# hwre.net
KiCad netlist of a schematic drawn in EAGLE
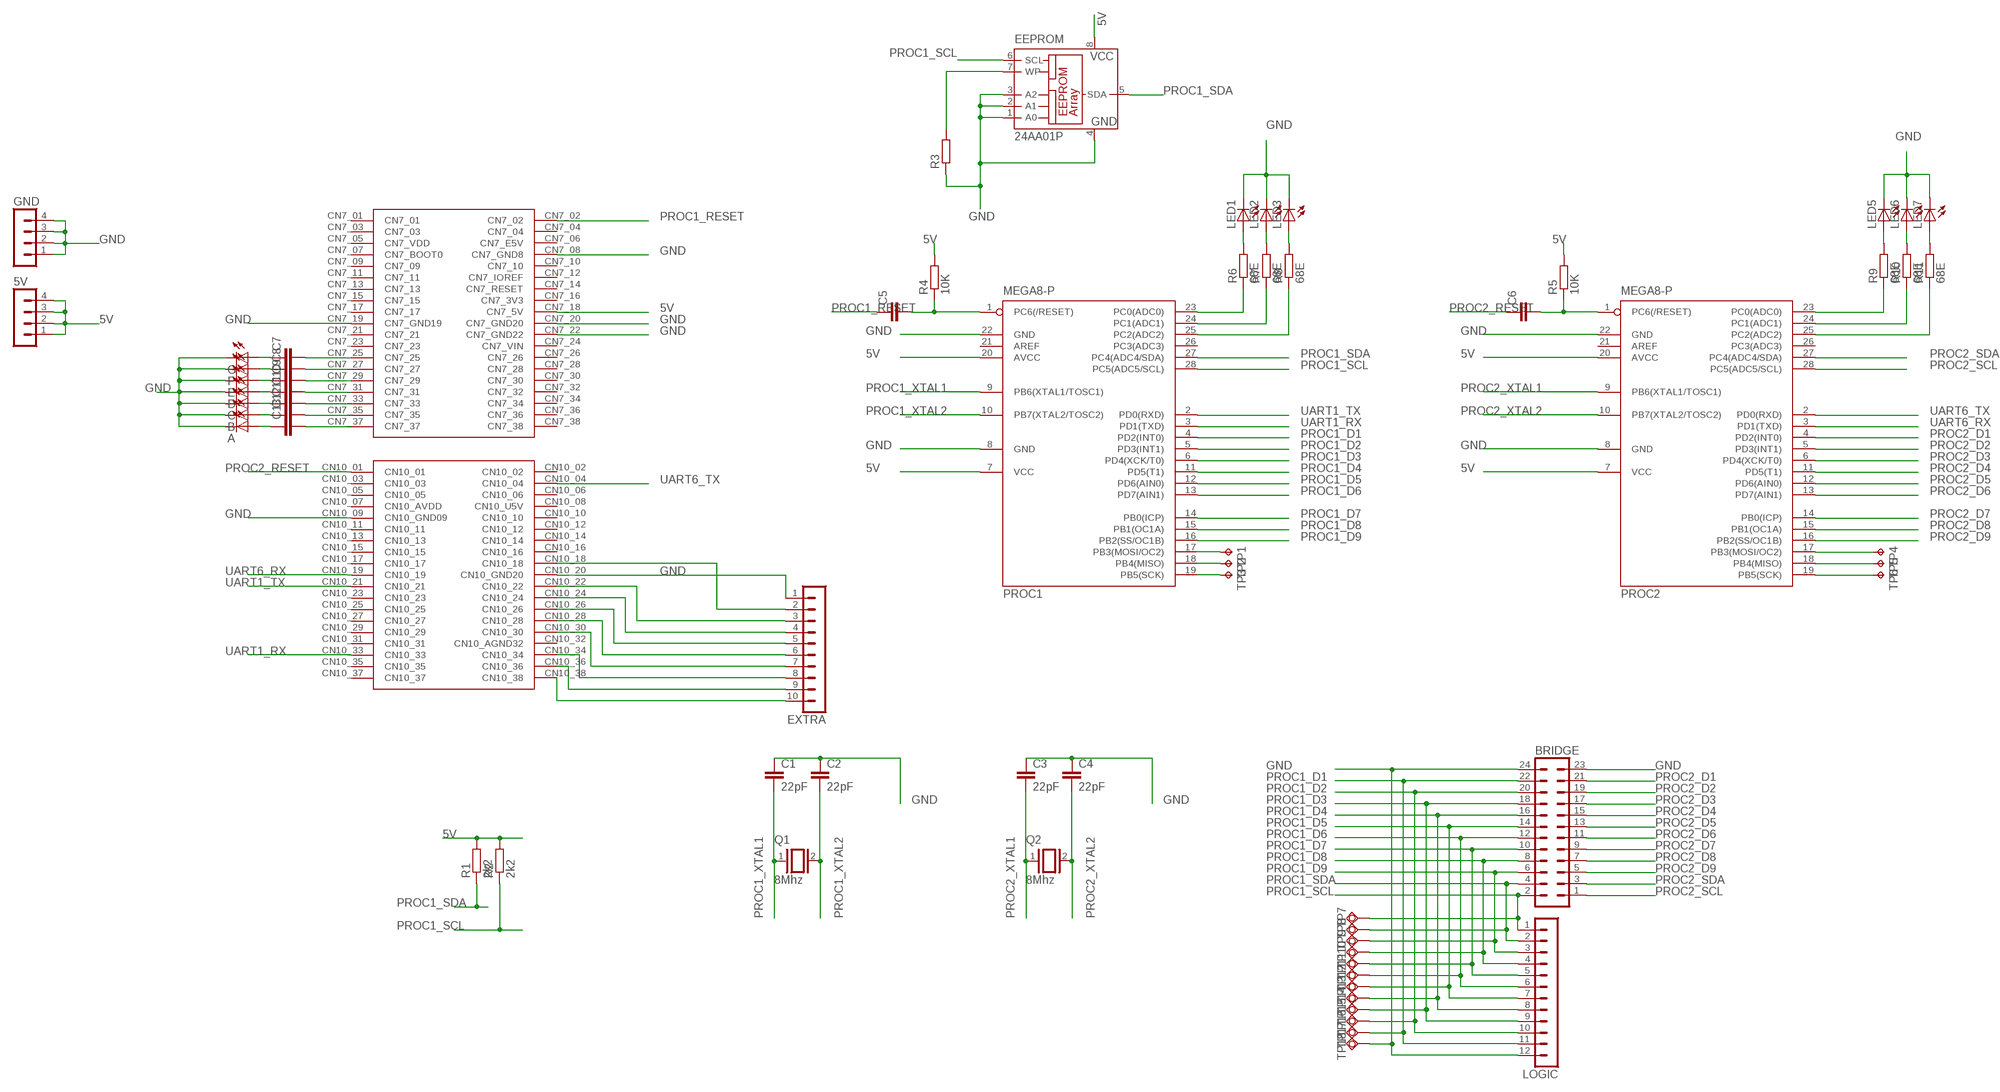
[diagram p0: schematic, sheet 1]

(export (version "E")
  (design (tool "Eeschema 10.0.6"))
  (components
    (comp (ref "5V")
      (value "MA04-1")
      (footprint "eagle-import:MA04-1")
      (libsource (lib "eagle-import") (part "MA04-1"))
    )
    (comp (ref "A")
      (value "LEDCHIP-LED0603")
      (footprint "eagle-import:CHIP-LED0603")
      (libsource (lib "eagle-import") (part "LEDCHIP-LED0603"))
    )
    (comp (ref "B")
      (value "LEDCHIP-LED0603")
      (footprint "eagle-import:CHIP-LED0603")
      (libsource (lib "eagle-import") (part "LEDCHIP-LED0603"))
    )
    (comp (ref "BRIDGE")
      (value "MA12-2")
      (footprint "eagle-import:MA12-2")
      (libsource (lib "eagle-import") (part "MA12-2"))
    )
    (comp (ref "C")
      (value "LEDCHIP-LED0603")
      (footprint "eagle-import:CHIP-LED0603")
      (libsource (lib "eagle-import") (part "LEDCHIP-LED0603"))
    )
    (comp (ref "C1")
      (value "22pF")
      (footprint "eagle-import:C0603")
      (libsource (lib "eagle-import") (part "C-EUC0603"))
    )
    (comp (ref "C2")
      (value "22pF")
      (footprint "eagle-import:C0603")
      (libsource (lib "eagle-import") (part "C-EUC0603"))
    )
    (comp (ref "C3")
      (value "22pF")
      (footprint "eagle-import:C0603")
      (libsource (lib "eagle-import") (part "C-EUC0603"))
    )
    (comp (ref "C4")
      (value "22pF")
      (footprint "eagle-import:C0603")
      (libsource (lib "eagle-import") (part "C-EUC0603"))
    )
    (comp (ref "C5")
      (value "C-EUC0603")
      (footprint "eagle-import:C0603")
      (libsource (lib "eagle-import") (part "C-EUC0603"))
    )
    (comp (ref "C6")
      (value "C-EUC0603")
      (footprint "eagle-import:C0603")
      (libsource (lib "eagle-import") (part "C-EUC0603"))
    )
    (comp (ref "C7")
      (value "C-EUC0603")
      (footprint "eagle-import:C0603")
      (libsource (lib "eagle-import") (part "C-EUC0603"))
    )
    (comp (ref "C8")
      (value "C-EUC0603")
      (footprint "eagle-import:C0603")
      (libsource (lib "eagle-import") (part "C-EUC0603"))
    )
    (comp (ref "C9")
      (value "C-EUC0603")
      (footprint "eagle-import:C0603")
      (libsource (lib "eagle-import") (part "C-EUC0603"))
    )
    (comp (ref "C10")
      (value "C-EUC0603")
      (footprint "eagle-import:C0603")
      (libsource (lib "eagle-import") (part "C-EUC0603"))
    )
    (comp (ref "C11")
      (value "C-EUC0603")
      (footprint "eagle-import:C0603")
      (libsource (lib "eagle-import") (part "C-EUC0603"))
    )
    (comp (ref "C12")
      (value "C-EUC0603")
      (footprint "eagle-import:C0603")
      (libsource (lib "eagle-import") (part "C-EUC0603"))
    )
    (comp (ref "C13")
      (value "C-EUC0603")
      (footprint "eagle-import:C0603")
      (libsource (lib "eagle-import") (part "C-EUC0603"))
    )
    (comp (ref "D")
      (value "LEDCHIP-LED0603")
      (footprint "eagle-import:CHIP-LED0603")
      (libsource (lib "eagle-import") (part "LEDCHIP-LED0603"))
    )
    (comp (ref "E")
      (value "LEDCHIP-LED0603")
      (footprint "eagle-import:CHIP-LED0603")
      (libsource (lib "eagle-import") (part "LEDCHIP-LED0603"))
    )
    (comp (ref "EEPROM")
      (value "24AA01P")
      (footprint "eagle-import:DIL8")
      (fields (field (name "MPN") "24AA01-I/P"))
      (libsource (lib "eagle-import") (part "24PAA01"))
    )
    (comp (ref "EXTRA")
      (value "MA10-1")
      (footprint "eagle-import:MA10-1")
      (libsource (lib "eagle-import") (part "MA10-1"))
    )
    (comp (ref "F")
      (value "LEDCHIP-LED0603")
      (footprint "eagle-import:CHIP-LED0603")
      (libsource (lib "eagle-import") (part "LEDCHIP-LED0603"))
    )
    (comp (ref "G")
      (value "LEDCHIP-LED0603")
      (footprint "eagle-import:CHIP-LED0603")
      (libsource (lib "eagle-import") (part "LEDCHIP-LED0603"))
    )
    (comp (ref "GND")
      (value "MA04-1")
      (footprint "eagle-import:MA04-1")
      (libsource (lib "eagle-import") (part "MA04-1"))
    )
    (comp (ref "LED1")
      (value "LEDSML0805")
      (footprint "eagle-import:SML0805")
      (libsource (lib "eagle-import") (part "LEDSML0805"))
    )
    (comp (ref "LED2")
      (value "LEDSML0805")
      (footprint "eagle-import:SML0805")
      (libsource (lib "eagle-import") (part "LEDSML0805"))
    )
    (comp (ref "LED3")
      (value "LEDSML0805")
      (footprint "eagle-import:SML0805")
      (libsource (lib "eagle-import") (part "LEDSML0805"))
    )
    (comp (ref "LED5")
      (value "LEDSML0805")
      (footprint "eagle-import:SML0805")
      (libsource (lib "eagle-import") (part "LEDSML0805"))
    )
    (comp (ref "LED6")
      (value "LEDSML0805")
      (footprint "eagle-import:SML0805")
      (libsource (lib "eagle-import") (part "LEDSML0805"))
    )
    (comp (ref "LED7")
      (value "LEDSML0805")
      (footprint "eagle-import:SML0805")
      (libsource (lib "eagle-import") (part "LEDSML0805"))
    )
    (comp (ref "LOGIC")
      (value "MA12-1")
      (footprint "eagle-import:MA12-1")
      (libsource (lib "eagle-import") (part "MA12-1"))
    )
    (comp (ref "PROC1")
      (value "MEGA8-P")
      (footprint "eagle-import:DIL28-3")
      (libsource (lib "eagle-import") (part "MEGA8-P"))
    )
    (comp (ref "PROC2")
      (value "MEGA8-P")
      (footprint "eagle-import:DIL28-3")
      (libsource (lib "eagle-import") (part "MEGA8-P"))
    )
    (comp (ref "Q1")
      (value "8Mhz")
      (footprint "eagle-import:QS")
      (libsource (lib "eagle-import") (part "XTAL/S"))
    )
    (comp (ref "Q2")
      (value "8Mhz")
      (footprint "eagle-import:QS")
      (libsource (lib "eagle-import") (part "XTAL/S"))
    )
    (comp (ref "R1")
      (value "2k2")
      (footprint "eagle-import:R0603")
      (libsource (lib "eagle-import") (part "R-EU_R0603"))
    )
    (comp (ref "R2")
      (value "2k2")
      (footprint "eagle-import:R0603")
      (libsource (lib "eagle-import") (part "R-EU_R0603"))
    )
    (comp (ref "R3")
      (value "R-EU_R0603")
      (footprint "eagle-import:R0603")
      (libsource (lib "eagle-import") (part "resistor_R-EU_R0603"))
    )
    (comp (ref "R4")
      (value "10K")
      (footprint "eagle-import:R0603")
      (libsource (lib "eagle-import") (part "resistor_R-EU_R0603"))
    )
    (comp (ref "R5")
      (value "10K")
      (footprint "eagle-import:R0603")
      (libsource (lib "eagle-import") (part "resistor_R-EU_R0603"))
    )
    (comp (ref "R6")
      (value "68E")
      (footprint "eagle-import:R0603")
      (libsource (lib "eagle-import") (part "R-EU_R0603"))
    )
    (comp (ref "R7")
      (value "68E")
      (footprint "eagle-import:R0603")
      (libsource (lib "eagle-import") (part "R-EU_R0603"))
    )
    (comp (ref "R8")
      (value "68E")
      (footprint "eagle-import:R0603")
      (libsource (lib "eagle-import") (part "R-EU_R0603"))
    )
    (comp (ref "R9")
      (value "68E")
      (footprint "eagle-import:R0603")
      (libsource (lib "eagle-import") (part "R-EU_R0603"))
    )
    (comp (ref "R10")
      (value "68E")
      (footprint "eagle-import:R0603")
      (libsource (lib "eagle-import") (part "R-EU_R0603"))
    )
    (comp (ref "R11")
      (value "68E")
      (footprint "eagle-import:R0603")
      (libsource (lib "eagle-import") (part "R-EU_R0603"))
    )
    (comp (ref "TP1")
      (value "TPTP20R")
      (footprint "eagle-import:TP20R")
      (libsource (lib "eagle-import") (part "TPTP20R"))
    )
    (comp (ref "TP2")
      (value "TPTP20R")
      (footprint "eagle-import:TP20R")
      (libsource (lib "eagle-import") (part "TPTP20R"))
    )
    (comp (ref "TP3")
      (value "TPTP20R")
      (footprint "eagle-import:TP20R")
      (libsource (lib "eagle-import") (part "TPTP20R"))
    )
    (comp (ref "TP4")
      (value "TPTP20R")
      (footprint "eagle-import:TP20R")
      (libsource (lib "eagle-import") (part "TPTP20R"))
    )
    (comp (ref "TP5")
      (value "TPTP20R")
      (footprint "eagle-import:TP20R")
      (libsource (lib "eagle-import") (part "TPTP20R"))
    )
    (comp (ref "TP6")
      (value "TPTP20R")
      (footprint "eagle-import:TP20R")
      (libsource (lib "eagle-import") (part "TPTP20R"))
    )
    (comp (ref "TP7")
      (value "TPSQTP20R")
      (footprint "eagle-import:TP20R")
      (libsource (lib "eagle-import") (part "TPSQTP20R"))
    )
    (comp (ref "TP8")
      (value "TPSQTP20R")
      (footprint "eagle-import:TP20R")
      (libsource (lib "eagle-import") (part "TPSQTP20R"))
    )
    (comp (ref "TP9")
      (value "TPSQTP20R")
      (footprint "eagle-import:TP20R")
      (libsource (lib "eagle-import") (part "TPSQTP20R"))
    )
    (comp (ref "TP10")
      (value "TPSQTP20R")
      (footprint "eagle-import:TP20R")
      (libsource (lib "eagle-import") (part "TPSQTP20R"))
    )
    (comp (ref "TP11")
      (value "TPSQTP20R")
      (footprint "eagle-import:TP20R")
      (libsource (lib "eagle-import") (part "TPSQTP20R"))
    )
    (comp (ref "TP12")
      (value "TPSQTP20R")
      (footprint "eagle-import:TP20R")
      (libsource (lib "eagle-import") (part "TPSQTP20R"))
    )
    (comp (ref "TP13")
      (value "TPSQTP20R")
      (footprint "eagle-import:TP20R")
      (libsource (lib "eagle-import") (part "TPSQTP20R"))
    )
    (comp (ref "TP14")
      (value "TPSQTP20R")
      (footprint "eagle-import:TP20R")
      (libsource (lib "eagle-import") (part "TPSQTP20R"))
    )
    (comp (ref "TP15")
      (value "TPSQTP20R")
      (footprint "eagle-import:TP20R")
      (libsource (lib "eagle-import") (part "TPSQTP20R"))
    )
    (comp (ref "TP16")
      (value "TPSQTP20R")
      (footprint "eagle-import:TP20R")
      (libsource (lib "eagle-import") (part "TPSQTP20R"))
    )
    (comp (ref "TP17")
      (value "TPSQTP20R")
      (footprint "eagle-import:TP20R")
      (libsource (lib "eagle-import") (part "TPSQTP20R"))
    )
    (comp (ref "TP18")
      (value "TPSQTP20R")
      (footprint "eagle-import:TP20R")
      (libsource (lib "eagle-import") (part "TPSQTP20R"))
    )
    (comp (ref "U$1")
      (value "NUCLEO_SHIELDGENERIC")
      (footprint "eagle-import:NUCLEO_SHIELD")
      (libsource (lib "eagle-import") (part "NUCLEO_SHIELDGENERIC"))
    )
  )
  (nets
    (net (code "1") (name "/5V") (class "Default")
      (node (ref "5V") (pin "1") (pinfunction "1_1") (pintype "passive"))
      (node (ref "5V") (pin "2") (pinfunction "2_2") (pintype "passive"))
      (node (ref "5V") (pin "3") (pinfunction "3_3") (pintype "passive"))
      (node (ref "5V") (pin "4") (pinfunction "4_4") (pintype "passive"))
      (node (ref "EEPROM") (pin "8") (pinfunction "VCC_8") (pintype "power_in"))
      (node (ref "PROC1") (pin "20") (pinfunction "AVCC_20") (pintype "power_in"))
      (node (ref "PROC1") (pin "7") (pinfunction "VCC_7") (pintype "power_in"))
      (node (ref "PROC2") (pin "20") (pinfunction "AVCC_20") (pintype "power_in"))
      (node (ref "PROC2") (pin "7") (pinfunction "VCC_7") (pintype "power_in"))
      (node (ref "R1") (pin "2") (pinfunction "2_2") (pintype "passive"))
      (node (ref "R2") (pin "2") (pinfunction "2_2") (pintype "passive"))
      (node (ref "R4") (pin "2") (pinfunction "2_2") (pintype "passive"))
      (node (ref "R5") (pin "2") (pinfunction "2_2") (pintype "passive"))
      (node (ref "U$1") (pin "CN7_18") (pinfunction "CN7_5V_CN7_18") (pintype "bidirectional"))
    )
    (net (code "2") (name "/GND") (class "Default")
      (node (ref "A") (pin "C") (pinfunction "C_C") (pintype "passive"))
      (node (ref "B") (pin "C") (pinfunction "C_C") (pintype "passive"))
      (node (ref "BRIDGE") (pin "23") (pinfunction "23_23") (pintype "passive"))
      (node (ref "BRIDGE") (pin "24") (pinfunction "24_24") (pintype "passive"))
      (node (ref "C") (pin "C") (pinfunction "C_C") (pintype "passive"))
      (node (ref "C1") (pin "1") (pinfunction "1_1") (pintype "passive"))
      (node (ref "C2") (pin "1") (pinfunction "1_1") (pintype "passive"))
      (node (ref "C3") (pin "1") (pinfunction "1_1") (pintype "passive"))
      (node (ref "C4") (pin "1") (pinfunction "1_1") (pintype "passive"))
      (node (ref "D") (pin "C") (pinfunction "C_C") (pintype "passive"))
      (node (ref "E") (pin "C") (pinfunction "C_C") (pintype "passive"))
      (node (ref "EEPROM") (pin "1") (pinfunction "A0_1") (pintype "input"))
      (node (ref "EEPROM") (pin "2") (pinfunction "A1_2") (pintype "input"))
      (node (ref "EEPROM") (pin "3") (pinfunction "A2_3") (pintype "input"))
      (node (ref "EEPROM") (pin "4") (pinfunction "GND_4") (pintype "power_in"))
      (node (ref "EXTRA") (pin "1") (pinfunction "1_1") (pintype "passive"))
      (node (ref "F") (pin "C") (pinfunction "C_C") (pintype "passive"))
      (node (ref "G") (pin "C") (pinfunction "C_C") (pintype "passive"))
      (node (ref "GND") (pin "1") (pinfunction "1_1") (pintype "passive"))
      (node (ref "GND") (pin "2") (pinfunction "2_2") (pintype "passive"))
      (node (ref "GND") (pin "3") (pinfunction "3_3") (pintype "passive"))
      (node (ref "GND") (pin "4") (pinfunction "4_4") (pintype "passive"))
      (node (ref "LED1") (pin "C") (pinfunction "C_C") (pintype "passive"))
      (node (ref "LED2") (pin "C") (pinfunction "C_C") (pintype "passive"))
      (node (ref "LED3") (pin "C") (pinfunction "C_C") (pintype "passive"))
      (node (ref "LED5") (pin "C") (pinfunction "C_C") (pintype "passive"))
      (node (ref "LED6") (pin "C") (pinfunction "C_C") (pintype "passive"))
      (node (ref "LED7") (pin "C") (pinfunction "C_C") (pintype "passive"))
      (node (ref "LOGIC") (pin "12") (pinfunction "12_12") (pintype "passive"))
      (node (ref "PROC1") (pin "22") (pinfunction "GND_22") (pintype "power_in"))
      (node (ref "PROC1") (pin "8") (pinfunction "GND_8") (pintype "power_in"))
      (node (ref "PROC2") (pin "22") (pinfunction "GND_22") (pintype "power_in"))
      (node (ref "PROC2") (pin "8") (pinfunction "GND_8") (pintype "power_in"))
      (node (ref "R3") (pin "1") (pinfunction "1_1") (pintype "passive"))
      (node (ref "TP18") (pin "TP") (pinfunction "TP_TP") (pintype "input"))
      (node (ref "U$1") (pin "CN10_09") (pinfunction "CN10_GND09_CN10_09") (pintype "bidirectional"))
      (node (ref "U$1") (pin "CN10_20") (pinfunction "CN10_GND20_CN10_20") (pintype "bidirectional"))
      (node (ref "U$1") (pin "CN7_08") (pinfunction "CN7_GND8_CN7_08") (pintype "bidirectional"))
      (node (ref "U$1") (pin "CN7_19") (pinfunction "CN7_GND19_CN7_19") (pintype "bidirectional"))
      (node (ref "U$1") (pin "CN7_20") (pinfunction "CN7_GND20_CN7_20") (pintype "bidirectional"))
      (node (ref "U$1") (pin "CN7_22") (pinfunction "CN7_GND22_CN7_22") (pintype "bidirectional"))
    )
    (net (code "3") (name "/PROC1_D1") (class "Default")
      (node (ref "BRIDGE") (pin "22") (pinfunction "22_22") (pintype "passive"))
      (node (ref "LOGIC") (pin "11") (pinfunction "11_11") (pintype "passive"))
      (node (ref "PROC1") (pin "4") (pinfunction "PD2(INT0)_4") (pintype "bidirectional"))
      (node (ref "TP17") (pin "TP") (pinfunction "TP_TP") (pintype "input"))
    )
    (net (code "4") (name "/PROC1_D2") (class "Default")
      (node (ref "BRIDGE") (pin "20") (pinfunction "20_20") (pintype "passive"))
      (node (ref "LOGIC") (pin "10") (pinfunction "10_10") (pintype "passive"))
      (node (ref "PROC1") (pin "5") (pinfunction "PD3(INT1)_5") (pintype "bidirectional"))
      (node (ref "TP16") (pin "TP") (pinfunction "TP_TP") (pintype "input"))
    )
    (net (code "5") (name "/PROC1_D3") (class "Default")
      (node (ref "BRIDGE") (pin "18") (pinfunction "18_18") (pintype "passive"))
      (node (ref "LOGIC") (pin "9") (pinfunction "9_9") (pintype "passive"))
      (node (ref "PROC1") (pin "6") (pinfunction "PD4(XCK/T0)_6") (pintype "bidirectional"))
      (node (ref "TP15") (pin "TP") (pinfunction "TP_TP") (pintype "input"))
    )
    (net (code "6") (name "/PROC1_D4") (class "Default")
      (node (ref "BRIDGE") (pin "16") (pinfunction "16_16") (pintype "passive"))
      (node (ref "LOGIC") (pin "8") (pinfunction "8_8") (pintype "passive"))
      (node (ref "PROC1") (pin "11") (pinfunction "PD5(T1)_11") (pintype "bidirectional"))
      (node (ref "TP14") (pin "TP") (pinfunction "TP_TP") (pintype "input"))
    )
    (net (code "7") (name "/PROC1_D5") (class "Default")
      (node (ref "BRIDGE") (pin "14") (pinfunction "14_14") (pintype "passive"))
      (node (ref "LOGIC") (pin "7") (pinfunction "7_7") (pintype "passive"))
      (node (ref "PROC1") (pin "12") (pinfunction "PD6(AIN0)_12") (pintype "bidirectional"))
      (node (ref "TP13") (pin "TP") (pinfunction "TP_TP") (pintype "input"))
    )
    (net (code "8") (name "/PROC1_D6") (class "Default")
      (node (ref "BRIDGE") (pin "12") (pinfunction "12_12") (pintype "passive"))
      (node (ref "LOGIC") (pin "6") (pinfunction "6_6") (pintype "passive"))
      (node (ref "PROC1") (pin "13") (pinfunction "PD7(AIN1)_13") (pintype "bidirectional"))
      (node (ref "TP12") (pin "TP") (pinfunction "TP_TP") (pintype "input"))
    )
    (net (code "9") (name "/PROC1_D7") (class "Default")
      (node (ref "BRIDGE") (pin "10") (pinfunction "10_10") (pintype "passive"))
      (node (ref "LOGIC") (pin "5") (pinfunction "5_5") (pintype "passive"))
      (node (ref "PROC1") (pin "14") (pinfunction "PB0(ICP)_14") (pintype "bidirectional"))
      (node (ref "TP11") (pin "TP") (pinfunction "TP_TP") (pintype "input"))
    )
    (net (code "10") (name "/PROC1_D8") (class "Default")
      (node (ref "BRIDGE") (pin "8") (pinfunction "8_8") (pintype "passive"))
      (node (ref "LOGIC") (pin "4") (pinfunction "4_4") (pintype "passive"))
      (node (ref "PROC1") (pin "15") (pinfunction "PB1(OC1A)_15") (pintype "bidirectional"))
      (node (ref "TP10") (pin "TP") (pinfunction "TP_TP") (pintype "input"))
    )
    (net (code "11") (name "/PROC1_D9") (class "Default")
      (node (ref "BRIDGE") (pin "6") (pinfunction "6_6") (pintype "passive"))
      (node (ref "LOGIC") (pin "3") (pinfunction "3_3") (pintype "passive"))
      (node (ref "PROC1") (pin "16") (pinfunction "PB2(SS/OC1B)_16") (pintype "bidirectional"))
      (node (ref "TP9") (pin "TP") (pinfunction "TP_TP") (pintype "input"))
    )
    (net (code "12") (name "/PROC1_RESET") (class "Default")
      (node (ref "C5") (pin "1") (pinfunction "1_1") (pintype "passive"))
      (node (ref "U$1") (pin "CN7_02") (pinfunction "CN7_02_CN7_02") (pintype "bidirectional"))
    )
    (net (code "13") (name "/PROC1_SCL") (class "Default")
      (node (ref "BRIDGE") (pin "2") (pinfunction "2_2") (pintype "passive"))
      (node (ref "EEPROM") (pin "6") (pinfunction "SCL_6") (pintype "input"))
      (node (ref "LOGIC") (pin "1") (pinfunction "1_1") (pintype "passive"))
      (node (ref "PROC1") (pin "28") (pinfunction "PC5(ADC5/SCL)_28") (pintype "bidirectional"))
      (node (ref "R2") (pin "1") (pinfunction "1_1") (pintype "passive"))
      (node (ref "TP7") (pin "TP") (pinfunction "TP_TP") (pintype "input"))
    )
    (net (code "14") (name "/PROC1_SDA") (class "Default")
      (node (ref "BRIDGE") (pin "4") (pinfunction "4_4") (pintype "passive"))
      (node (ref "EEPROM") (pin "5") (pinfunction "SDA_5") (pintype "bidirectional"))
      (node (ref "LOGIC") (pin "2") (pinfunction "2_2") (pintype "passive"))
      (node (ref "PROC1") (pin "27") (pinfunction "PC4(ADC4/SDA)_27") (pintype "bidirectional"))
      (node (ref "R1") (pin "1") (pinfunction "1_1") (pintype "passive"))
      (node (ref "TP8") (pin "TP") (pinfunction "TP_TP") (pintype "input"))
    )
    (net (code "15") (name "/PROC1_XTAL1") (class "Default")
      (node (ref "C1") (pin "2") (pinfunction "2_2") (pintype "passive"))
      (node (ref "PROC1") (pin "9") (pinfunction "PB6(XTAL1/TOSC1)_9") (pintype "bidirectional"))
      (node (ref "Q1") (pin "1") (pinfunction "1_1") (pintype "passive"))
    )
    (net (code "16") (name "/PROC1_XTAL2") (class "Default")
      (node (ref "C2") (pin "2") (pinfunction "2_2") (pintype "passive"))
      (node (ref "PROC1") (pin "10") (pinfunction "PB7(XTAL2/TOSC2)_10") (pintype "bidirectional"))
      (node (ref "Q1") (pin "2") (pinfunction "2_2") (pintype "passive"))
    )
    (net (code "17") (name "/PROC2_D1") (class "Default")
      (node (ref "BRIDGE") (pin "21") (pinfunction "21_21") (pintype "passive"))
      (node (ref "PROC2") (pin "4") (pinfunction "PD2(INT0)_4") (pintype "bidirectional"))
    )
    (net (code "18") (name "/PROC2_D2") (class "Default")
      (node (ref "BRIDGE") (pin "19") (pinfunction "19_19") (pintype "passive"))
      (node (ref "PROC2") (pin "5") (pinfunction "PD3(INT1)_5") (pintype "bidirectional"))
    )
    (net (code "19") (name "/PROC2_D3") (class "Default")
      (node (ref "BRIDGE") (pin "17") (pinfunction "17_17") (pintype "passive"))
      (node (ref "PROC2") (pin "6") (pinfunction "PD4(XCK/T0)_6") (pintype "bidirectional"))
    )
    (net (code "20") (name "/PROC2_D4") (class "Default")
      (node (ref "BRIDGE") (pin "15") (pinfunction "15_15") (pintype "passive"))
      (node (ref "PROC2") (pin "11") (pinfunction "PD5(T1)_11") (pintype "bidirectional"))
    )
    (net (code "21") (name "/PROC2_D5") (class "Default")
      (node (ref "BRIDGE") (pin "13") (pinfunction "13_13") (pintype "passive"))
      (node (ref "PROC2") (pin "12") (pinfunction "PD6(AIN0)_12") (pintype "bidirectional"))
    )
    (net (code "22") (name "/PROC2_D6") (class "Default")
      (node (ref "BRIDGE") (pin "11") (pinfunction "11_11") (pintype "passive"))
      (node (ref "PROC2") (pin "13") (pinfunction "PD7(AIN1)_13") (pintype "bidirectional"))
    )
    (net (code "23") (name "/PROC2_D7") (class "Default")
      (node (ref "BRIDGE") (pin "9") (pinfunction "9_9") (pintype "passive"))
      (node (ref "PROC2") (pin "14") (pinfunction "PB0(ICP)_14") (pintype "bidirectional"))
    )
    (net (code "24") (name "/PROC2_D8") (class "Default")
      (node (ref "BRIDGE") (pin "7") (pinfunction "7_7") (pintype "passive"))
      (node (ref "PROC2") (pin "15") (pinfunction "PB1(OC1A)_15") (pintype "bidirectional"))
    )
    (net (code "25") (name "/PROC2_D9") (class "Default")
      (node (ref "BRIDGE") (pin "5") (pinfunction "5_5") (pintype "passive"))
      (node (ref "PROC2") (pin "16") (pinfunction "PB2(SS/OC1B)_16") (pintype "bidirectional"))
    )
    (net (code "26") (name "/PROC2_RESET") (class "Default")
      (node (ref "C6") (pin "1") (pinfunction "1_1") (pintype "passive"))
      (node (ref "U$1") (pin "CN10_01") (pinfunction "CN10_01_CN10_01") (pintype "bidirectional"))
    )
    (net (code "27") (name "/PROC2_SCL") (class "Default")
      (node (ref "BRIDGE") (pin "1") (pinfunction "1_1") (pintype "passive"))
      (node (ref "PROC2") (pin "28") (pinfunction "PC5(ADC5/SCL)_28") (pintype "bidirectional"))
    )
    (net (code "28") (name "/PROC2_SDA") (class "Default")
      (node (ref "BRIDGE") (pin "3") (pinfunction "3_3") (pintype "passive"))
      (node (ref "PROC2") (pin "27") (pinfunction "PC4(ADC4/SDA)_27") (pintype "bidirectional"))
    )
    (net (code "29") (name "/PROC2_XTAL1") (class "Default")
      (node (ref "C3") (pin "2") (pinfunction "2_2") (pintype "passive"))
      (node (ref "PROC2") (pin "9") (pinfunction "PB6(XTAL1/TOSC1)_9") (pintype "bidirectional"))
      (node (ref "Q2") (pin "1") (pinfunction "1_1") (pintype "passive"))
    )
    (net (code "30") (name "/PROC2_XTAL2") (class "Default")
      (node (ref "C4") (pin "2") (pinfunction "2_2") (pintype "passive"))
      (node (ref "PROC2") (pin "10") (pinfunction "PB7(XTAL2/TOSC2)_10") (pintype "bidirectional"))
      (node (ref "Q2") (pin "2") (pinfunction "2_2") (pintype "passive"))
    )
    (net (code "31") (name "/UART1_RX") (class "Default")
      (node (ref "PROC1") (pin "3") (pinfunction "PD1(TXD)_3") (pintype "bidirectional"))
      (node (ref "U$1") (pin "CN10_33") (pinfunction "CN10_33_CN10_33") (pintype "bidirectional"))
    )
    (net (code "32") (name "/UART1_TX") (class "Default")
      (node (ref "PROC1") (pin "2") (pinfunction "PD0(RXD)_2") (pintype "bidirectional"))
      (node (ref "U$1") (pin "CN10_21") (pinfunction "CN10_21_CN10_21") (pintype "bidirectional"))
    )
    (net (code "33") (name "/UART6_RX") (class "Default")
      (node (ref "PROC2") (pin "3") (pinfunction "PD1(TXD)_3") (pintype "bidirectional"))
      (node (ref "U$1") (pin "CN10_19") (pinfunction "CN10_19_CN10_19") (pintype "bidirectional"))
    )
    (net (code "34") (name "/UART6_TX") (class "Default")
      (node (ref "PROC2") (pin "2") (pinfunction "PD0(RXD)_2") (pintype "bidirectional"))
      (node (ref "U$1") (pin "CN10_04") (pinfunction "CN10_04_CN10_04") (pintype "bidirectional"))
    )
    (net (code "35") (name "Net-(A-PadA)") (class "Default")
      (node (ref "A") (pin "A") (pinfunction "A_A") (pintype "passive"))
      (node (ref "C13") (pin "1") (pinfunction "1_1") (pintype "passive"))
    )
    (net (code "36") (name "Net-(B-PadA)") (class "Default")
      (node (ref "B") (pin "A") (pinfunction "A_A") (pintype "passive"))
      (node (ref "C12") (pin "1") (pinfunction "1_1") (pintype "passive"))
    )
    (net (code "37") (name "Net-(C-PadA)") (class "Default")
      (node (ref "C") (pin "A") (pinfunction "A_A") (pintype "passive"))
      (node (ref "C11") (pin "1") (pinfunction "1_1") (pintype "passive"))
    )
    (net (code "38") (name "Net-(C7-Pad1)") (class "Default")
      (node (ref "C7") (pin "1") (pinfunction "1_1") (pintype "passive"))
      (node (ref "G") (pin "A") (pinfunction "A_A") (pintype "passive"))
    )
    (net (code "39") (name "Net-(C7-Pad2)") (class "Default")
      (node (ref "C7") (pin "2") (pinfunction "2_2") (pintype "passive"))
      (node (ref "U$1") (pin "CN7_25") (pinfunction "CN7_25_CN7_25") (pintype "bidirectional"))
    )
    (net (code "40") (name "Net-(C8-Pad1)") (class "Default")
      (node (ref "C8") (pin "1") (pinfunction "1_1") (pintype "passive"))
      (node (ref "F") (pin "A") (pinfunction "A_A") (pintype "passive"))
    )
    (net (code "41") (name "Net-(C8-Pad2)") (class "Default")
      (node (ref "C8") (pin "2") (pinfunction "2_2") (pintype "passive"))
      (node (ref "U$1") (pin "CN7_27") (pinfunction "CN7_27_CN7_27") (pintype "bidirectional"))
    )
    (net (code "42") (name "Net-(C9-Pad1)") (class "Default")
      (node (ref "C9") (pin "1") (pinfunction "1_1") (pintype "passive"))
      (node (ref "E") (pin "A") (pinfunction "A_A") (pintype "passive"))
    )
    (net (code "43") (name "Net-(C9-Pad2)") (class "Default")
      (node (ref "C9") (pin "2") (pinfunction "2_2") (pintype "passive"))
      (node (ref "U$1") (pin "CN7_29") (pinfunction "CN7_29_CN7_29") (pintype "bidirectional"))
    )
    (net (code "44") (name "Net-(C10-Pad1)") (class "Default")
      (node (ref "C10") (pin "1") (pinfunction "1_1") (pintype "passive"))
      (node (ref "D") (pin "A") (pinfunction "A_A") (pintype "passive"))
    )
    (net (code "45") (name "Net-(C10-Pad2)") (class "Default")
      (node (ref "C10") (pin "2") (pinfunction "2_2") (pintype "passive"))
      (node (ref "U$1") (pin "CN7_31") (pinfunction "CN7_31_CN7_31") (pintype "bidirectional"))
    )
    (net (code "46") (name "Net-(C11-Pad2)") (class "Default")
      (node (ref "C11") (pin "2") (pinfunction "2_2") (pintype "passive"))
      (node (ref "U$1") (pin "CN7_33") (pinfunction "CN7_33_CN7_33") (pintype "bidirectional"))
    )
    (net (code "47") (name "Net-(C12-Pad2)") (class "Default")
      (node (ref "C12") (pin "2") (pinfunction "2_2") (pintype "passive"))
      (node (ref "U$1") (pin "CN7_35") (pinfunction "CN7_35_CN7_35") (pintype "bidirectional"))
    )
    (net (code "48") (name "Net-(C13-Pad2)") (class "Default")
      (node (ref "C13") (pin "2") (pinfunction "2_2") (pintype "passive"))
      (node (ref "U$1") (pin "CN7_37") (pinfunction "CN7_37_CN7_37") (pintype "bidirectional"))
    )
    (net (code "49") (name "Net-(EEPROM-WP)") (class "Default")
      (node (ref "EEPROM") (pin "7") (pinfunction "WP_7") (pintype "input"))
      (node (ref "R3") (pin "2") (pinfunction "2_2") (pintype "passive"))
    )
    (net (code "50") (name "Net-(EXTRA-Pad2)") (class "Default")
      (node (ref "EXTRA") (pin "2") (pinfunction "2_2") (pintype "passive"))
      (node (ref "U$1") (pin "CN10_18") (pinfunction "CN10_18_CN10_18") (pintype "bidirectional"))
    )
    (net (code "51") (name "Net-(EXTRA-Pad3)") (class "Default")
      (node (ref "EXTRA") (pin "3") (pinfunction "3_3") (pintype "passive"))
      (node (ref "U$1") (pin "CN10_22") (pinfunction "CN10_22_CN10_22") (pintype "bidirectional"))
    )
    (net (code "52") (name "Net-(EXTRA-Pad4)") (class "Default")
      (node (ref "EXTRA") (pin "4") (pinfunction "4_4") (pintype "passive"))
      (node (ref "U$1") (pin "CN10_24") (pinfunction "CN10_24_CN10_24") (pintype "bidirectional"))
    )
    (net (code "53") (name "Net-(EXTRA-Pad5)") (class "Default")
      (node (ref "EXTRA") (pin "5") (pinfunction "5_5") (pintype "passive"))
      (node (ref "U$1") (pin "CN10_26") (pinfunction "CN10_26_CN10_26") (pintype "bidirectional"))
    )
    (net (code "54") (name "Net-(EXTRA-Pad6)") (class "Default")
      (node (ref "EXTRA") (pin "6") (pinfunction "6_6") (pintype "passive"))
      (node (ref "U$1") (pin "CN10_28") (pinfunction "CN10_28_CN10_28") (pintype "bidirectional"))
    )
    (net (code "55") (name "Net-(EXTRA-Pad7)") (class "Default")
      (node (ref "EXTRA") (pin "7") (pinfunction "7_7") (pintype "passive"))
      (node (ref "U$1") (pin "CN10_30") (pinfunction "CN10_30_CN10_30") (pintype "bidirectional"))
    )
    (net (code "56") (name "Net-(EXTRA-Pad8)") (class "Default")
      (node (ref "EXTRA") (pin "8") (pinfunction "8_8") (pintype "passive"))
      (node (ref "U$1") (pin "CN10_34") (pinfunction "CN10_34_CN10_34") (pintype "bidirectional"))
    )
    (net (code "57") (name "Net-(EXTRA-Pad9)") (class "Default")
      (node (ref "EXTRA") (pin "9") (pinfunction "9_9") (pintype "passive"))
      (node (ref "U$1") (pin "CN10_36") (pinfunction "CN10_36_CN10_36") (pintype "bidirectional"))
    )
    (net (code "58") (name "Net-(EXTRA-Pad10)") (class "Default")
      (node (ref "EXTRA") (pin "10") (pinfunction "10_10") (pintype "passive"))
      (node (ref "U$1") (pin "CN10_38") (pinfunction "CN10_38_CN10_38") (pintype "bidirectional"))
    )
    (net (code "59") (name "Net-(LED1-PadA)") (class "Default")
      (node (ref "LED1") (pin "A") (pinfunction "A_A") (pintype "passive"))
      (node (ref "R6") (pin "2") (pinfunction "2_2") (pintype "passive"))
    )
    (net (code "60") (name "Net-(LED2-PadA)") (class "Default")
      (node (ref "LED2") (pin "A") (pinfunction "A_A") (pintype "passive"))
      (node (ref "R7") (pin "2") (pinfunction "2_2") (pintype "passive"))
    )
    (net (code "61") (name "Net-(LED3-PadA)") (class "Default")
      (node (ref "LED3") (pin "A") (pinfunction "A_A") (pintype "passive"))
      (node (ref "R8") (pin "2") (pinfunction "2_2") (pintype "passive"))
    )
    (net (code "62") (name "Net-(LED5-PadA)") (class "Default")
      (node (ref "LED5") (pin "A") (pinfunction "A_A") (pintype "passive"))
      (node (ref "R9") (pin "2") (pinfunction "2_2") (pintype "passive"))
    )
    (net (code "63") (name "Net-(LED6-PadA)") (class "Default")
      (node (ref "LED6") (pin "A") (pinfunction "A_A") (pintype "passive"))
      (node (ref "R10") (pin "2") (pinfunction "2_2") (pintype "passive"))
    )
    (net (code "64") (name "Net-(LED7-PadA)") (class "Default")
      (node (ref "LED7") (pin "A") (pinfunction "A_A") (pintype "passive"))
      (node (ref "R11") (pin "2") (pinfunction "2_2") (pintype "passive"))
    )
    (net (code "65") (name "Net-(PROC1-PB3(MOSI{slash}OC2))") (class "Default")
      (node (ref "PROC1") (pin "17") (pinfunction "PB3(MOSI/OC2)_17") (pintype "bidirectional"))
      (node (ref "TP1") (pin "TP") (pinfunction "TP_TP") (pintype "input"))
    )
    (net (code "66") (name "Net-(PROC1-PB4(MISO))") (class "Default")
      (node (ref "PROC1") (pin "18") (pinfunction "PB4(MISO)_18") (pintype "bidirectional"))
      (node (ref "TP2") (pin "TP") (pinfunction "TP_TP") (pintype "input"))
    )
    (net (code "67") (name "Net-(PROC1-PB5(SCK))") (class "Default")
      (node (ref "PROC1") (pin "19") (pinfunction "PB5(SCK)_19") (pintype "bidirectional"))
      (node (ref "TP3") (pin "TP") (pinfunction "TP_TP") (pintype "input"))
    )
    (net (code "68") (name "Net-(PROC1-PC0(ADC0))") (class "Default")
      (node (ref "PROC1") (pin "23") (pinfunction "PC0(ADC0)_23") (pintype "bidirectional"))
      (node (ref "R6") (pin "1") (pinfunction "1_1") (pintype "passive"))
    )
    (net (code "69") (name "Net-(PROC1-PC1(ADC1))") (class "Default")
      (node (ref "PROC1") (pin "24") (pinfunction "PC1(ADC1)_24") (pintype "bidirectional"))
      (node (ref "R7") (pin "1") (pinfunction "1_1") (pintype "passive"))
    )
    (net (code "70") (name "Net-(PROC1-PC2(ADC2))") (class "Default")
      (node (ref "PROC1") (pin "25") (pinfunction "PC2(ADC2)_25") (pintype "bidirectional"))
      (node (ref "R8") (pin "1") (pinfunction "1_1") (pintype "passive"))
    )
    (net (code "71") (name "Net-(PROC1-PC6({slash}RESET))") (class "Default")
      (node (ref "C5") (pin "2") (pinfunction "2_2") (pintype "passive"))
      (node (ref "PROC1") (pin "1") (pinfunction "PC6(/RESET)_1") (pintype "bidirectional"))
      (node (ref "R4") (pin "1") (pinfunction "1_1") (pintype "passive"))
    )
    (net (code "72") (name "Net-(PROC2-PB3(MOSI{slash}OC2))") (class "Default")
      (node (ref "PROC2") (pin "17") (pinfunction "PB3(MOSI/OC2)_17") (pintype "bidirectional"))
      (node (ref "TP4") (pin "TP") (pinfunction "TP_TP") (pintype "input"))
    )
    (net (code "73") (name "Net-(PROC2-PB4(MISO))") (class "Default")
      (node (ref "PROC2") (pin "18") (pinfunction "PB4(MISO)_18") (pintype "bidirectional"))
      (node (ref "TP5") (pin "TP") (pinfunction "TP_TP") (pintype "input"))
    )
    (net (code "74") (name "Net-(PROC2-PB5(SCK))") (class "Default")
      (node (ref "PROC2") (pin "19") (pinfunction "PB5(SCK)_19") (pintype "bidirectional"))
      (node (ref "TP6") (pin "TP") (pinfunction "TP_TP") (pintype "input"))
    )
    (net (code "75") (name "Net-(PROC2-PC0(ADC0))") (class "Default")
      (node (ref "PROC2") (pin "23") (pinfunction "PC0(ADC0)_23") (pintype "bidirectional"))
      (node (ref "R9") (pin "1") (pinfunction "1_1") (pintype "passive"))
    )
    (net (code "76") (name "Net-(PROC2-PC1(ADC1))") (class "Default")
      (node (ref "PROC2") (pin "24") (pinfunction "PC1(ADC1)_24") (pintype "bidirectional"))
      (node (ref "R10") (pin "1") (pinfunction "1_1") (pintype "passive"))
    )
    (net (code "77") (name "Net-(PROC2-PC2(ADC2))") (class "Default")
      (node (ref "PROC2") (pin "25") (pinfunction "PC2(ADC2)_25") (pintype "bidirectional"))
      (node (ref "R11") (pin "1") (pinfunction "1_1") (pintype "passive"))
    )
    (net (code "78") (name "Net-(PROC2-PC6({slash}RESET))") (class "Default")
      (node (ref "C6") (pin "2") (pinfunction "2_2") (pintype "passive"))
      (node (ref "PROC2") (pin "1") (pinfunction "PC6(/RESET)_1") (pintype "bidirectional"))
      (node (ref "R5") (pin "1") (pinfunction "1_1") (pintype "passive"))
    )
    (net (code "79") (name "unconnected-(PROC1-AREF-Pad21)") (class "Default")
      (node (ref "PROC1") (pin "21") (pinfunction "AREF_21") (pintype "passive"))
    )
    (net (code "80") (name "unconnected-(PROC1-PC3(ADC3)-Pad26)") (class "Default")
      (node (ref "PROC1") (pin "26") (pinfunction "PC3(ADC3)_26") (pintype "bidirectional"))
    )
    (net (code "81") (name "unconnected-(PROC2-AREF-Pad21)") (class "Default")
      (node (ref "PROC2") (pin "21") (pinfunction "AREF_21") (pintype "passive"))
    )
    (net (code "82") (name "unconnected-(PROC2-PC3(ADC3)-Pad26)") (class "Default")
      (node (ref "PROC2") (pin "26") (pinfunction "PC3(ADC3)_26") (pintype "bidirectional"))
    )
    (net (code "83") (name "unconnected-(U$1-CN7_3V3-PadCN7_16)") (class "Default")
      (node (ref "U$1") (pin "CN7_16") (pinfunction "CN7_3V3_CN7_16") (pintype "bidirectional"))
    )
    (net (code "84") (name "unconnected-(U$1-CN7_BOOT0-PadCN7_07)") (class "Default")
      (node (ref "U$1") (pin "CN7_07") (pinfunction "CN7_BOOT0_CN7_07") (pintype "bidirectional"))
    )
    (net (code "85") (name "unconnected-(U$1-CN7_E5V-PadCN7_06)") (class "Default")
      (node (ref "U$1") (pin "CN7_06") (pinfunction "CN7_E5V_CN7_06") (pintype "bidirectional"))
    )
    (net (code "86") (name "unconnected-(U$1-CN7_IOREF-PadCN7_12)") (class "Default")
      (node (ref "U$1") (pin "CN7_12") (pinfunction "CN7_IOREF_CN7_12") (pintype "bidirectional"))
    )
    (net (code "87") (name "unconnected-(U$1-CN7_RESET-PadCN7_14)") (class "Default")
      (node (ref "U$1") (pin "CN7_14") (pinfunction "CN7_RESET_CN7_14") (pintype "bidirectional"))
    )
    (net (code "88") (name "unconnected-(U$1-CN7_VDD-PadCN7_05)") (class "Default")
      (node (ref "U$1") (pin "CN7_05") (pinfunction "CN7_VDD_CN7_05") (pintype "bidirectional"))
    )
    (net (code "89") (name "unconnected-(U$1-CN7_VIN-PadCN7_24)") (class "Default")
      (node (ref "U$1") (pin "CN7_24") (pinfunction "CN7_VIN_CN7_24") (pintype "bidirectional"))
    )
    (net (code "90") (name "unconnected-(U$1-CN10_AGND32-PadCN10_32)") (class "Default")
      (node (ref "U$1") (pin "CN10_32") (pinfunction "CN10_AGND32_CN10_32") (pintype "bidirectional"))
    )
    (net (code "91") (name "unconnected-(U$1-CN10_AVDD-PadCN10_07)") (class "Default")
      (node (ref "U$1") (pin "CN10_07") (pinfunction "CN10_AVDD_CN10_07") (pintype "bidirectional"))
    )
    (net (code "92") (name "unconnected-(U$1-CN10_U5V-PadCN10_08)") (class "Default")
      (node (ref "U$1") (pin "CN10_08") (pinfunction "CN10_U5V_CN10_08") (pintype "bidirectional"))
    )
    (net (code "93") (name "unconnected-(U$1-PadCN7_01)") (class "Default")
      (node (ref "U$1") (pin "CN7_01") (pinfunction "CN7_01_CN7_01") (pintype "bidirectional"))
    )
    (net (code "94") (name "unconnected-(U$1-PadCN7_03)") (class "Default")
      (node (ref "U$1") (pin "CN7_03") (pinfunction "CN7_03_CN7_03") (pintype "bidirectional"))
    )
    (net (code "95") (name "unconnected-(U$1-PadCN7_04)") (class "Default")
      (node (ref "U$1") (pin "CN7_04") (pinfunction "CN7_04_CN7_04") (pintype "bidirectional"))
    )
    (net (code "96") (name "unconnected-(U$1-PadCN7_09)") (class "Default")
      (node (ref "U$1") (pin "CN7_09") (pinfunction "CN7_09_CN7_09") (pintype "bidirectional"))
    )
    (net (code "97") (name "unconnected-(U$1-PadCN7_10)") (class "Default")
      (node (ref "U$1") (pin "CN7_10") (pinfunction "CN7_10_CN7_10") (pintype "bidirectional"))
    )
    (net (code "98") (name "unconnected-(U$1-PadCN7_11)") (class "Default")
      (node (ref "U$1") (pin "CN7_11") (pinfunction "CN7_11_CN7_11") (pintype "bidirectional"))
    )
    (net (code "99") (name "unconnected-(U$1-PadCN7_13)") (class "Default")
      (node (ref "U$1") (pin "CN7_13") (pinfunction "CN7_13_CN7_13") (pintype "bidirectional"))
    )
    (net (code "100") (name "unconnected-(U$1-PadCN7_15)") (class "Default")
      (node (ref "U$1") (pin "CN7_15") (pinfunction "CN7_15_CN7_15") (pintype "bidirectional"))
    )
    (net (code "101") (name "unconnected-(U$1-PadCN7_17)") (class "Default")
      (node (ref "U$1") (pin "CN7_17") (pinfunction "CN7_17_CN7_17") (pintype "bidirectional"))
    )
    (net (code "102") (name "unconnected-(U$1-PadCN7_21)") (class "Default")
      (node (ref "U$1") (pin "CN7_21") (pinfunction "CN7_21_CN7_21") (pintype "bidirectional"))
    )
    (net (code "103") (name "unconnected-(U$1-PadCN7_23)") (class "Default")
      (node (ref "U$1") (pin "CN7_23") (pinfunction "CN7_23_CN7_23") (pintype "bidirectional"))
    )
    (net (code "104") (name "unconnected-(U$1-PadCN7_26)") (class "Default")
      (node (ref "U$1") (pin "CN7_26") (pinfunction "CN7_26_CN7_26") (pintype "bidirectional"))
    )
    (net (code "105") (name "unconnected-(U$1-PadCN7_28)") (class "Default")
      (node (ref "U$1") (pin "CN7_28") (pinfunction "CN7_28_CN7_28") (pintype "bidirectional"))
    )
    (net (code "106") (name "unconnected-(U$1-PadCN7_30)") (class "Default")
      (node (ref "U$1") (pin "CN7_30") (pinfunction "CN7_30_CN7_30") (pintype "bidirectional"))
    )
    (net (code "107") (name "unconnected-(U$1-PadCN7_32)") (class "Default")
      (node (ref "U$1") (pin "CN7_32") (pinfunction "CN7_32_CN7_32") (pintype "bidirectional"))
    )
    (net (code "108") (name "unconnected-(U$1-PadCN7_34)") (class "Default")
      (node (ref "U$1") (pin "CN7_34") (pinfunction "CN7_34_CN7_34") (pintype "bidirectional"))
    )
    (net (code "109") (name "unconnected-(U$1-PadCN7_36)") (class "Default")
      (node (ref "U$1") (pin "CN7_36") (pinfunction "CN7_36_CN7_36") (pintype "bidirectional"))
    )
    (net (code "110") (name "unconnected-(U$1-PadCN7_38)") (class "Default")
      (node (ref "U$1") (pin "CN7_38") (pinfunction "CN7_38_CN7_38") (pintype "bidirectional"))
    )
    (net (code "111") (name "unconnected-(U$1-PadCN10_02)") (class "Default")
      (node (ref "U$1") (pin "CN10_02") (pinfunction "CN10_02_CN10_02") (pintype "bidirectional"))
    )
    (net (code "112") (name "unconnected-(U$1-PadCN10_03)") (class "Default")
      (node (ref "U$1") (pin "CN10_03") (pinfunction "CN10_03_CN10_03") (pintype "bidirectional"))
    )
    (net (code "113") (name "unconnected-(U$1-PadCN10_05)") (class "Default")
      (node (ref "U$1") (pin "CN10_05") (pinfunction "CN10_05_CN10_05") (pintype "bidirectional"))
    )
    (net (code "114") (name "unconnected-(U$1-PadCN10_06)") (class "Default")
      (node (ref "U$1") (pin "CN10_06") (pinfunction "CN10_06_CN10_06") (pintype "bidirectional"))
    )
    (net (code "115") (name "unconnected-(U$1-PadCN10_10)") (class "Default")
      (node (ref "U$1") (pin "CN10_10") (pinfunction "CN10_10_CN10_10") (pintype "bidirectional"))
    )
    (net (code "116") (name "unconnected-(U$1-PadCN10_11)") (class "Default")
      (node (ref "U$1") (pin "CN10_11") (pinfunction "CN10_11_CN10_11") (pintype "bidirectional"))
    )
    (net (code "117") (name "unconnected-(U$1-PadCN10_12)") (class "Default")
      (node (ref "U$1") (pin "CN10_12") (pinfunction "CN10_12_CN10_12") (pintype "bidirectional"))
    )
    (net (code "118") (name "unconnected-(U$1-PadCN10_13)") (class "Default")
      (node (ref "U$1") (pin "CN10_13") (pinfunction "CN10_13_CN10_13") (pintype "bidirectional"))
    )
    (net (code "119") (name "unconnected-(U$1-PadCN10_14)") (class "Default")
      (node (ref "U$1") (pin "CN10_14") (pinfunction "CN10_14_CN10_14") (pintype "bidirectional"))
    )
    (net (code "120") (name "unconnected-(U$1-PadCN10_15)") (class "Default")
      (node (ref "U$1") (pin "CN10_15") (pinfunction "CN10_15_CN10_15") (pintype "bidirectional"))
    )
    (net (code "121") (name "unconnected-(U$1-PadCN10_16)") (class "Default")
      (node (ref "U$1") (pin "CN10_16") (pinfunction "CN10_16_CN10_16") (pintype "bidirectional"))
    )
    (net (code "122") (name "unconnected-(U$1-PadCN10_17)") (class "Default")
      (node (ref "U$1") (pin "CN10_17") (pinfunction "CN10_17_CN10_17") (pintype "bidirectional"))
    )
    (net (code "123") (name "unconnected-(U$1-PadCN10_23)") (class "Default")
      (node (ref "U$1") (pin "CN10_23") (pinfunction "CN10_23_CN10_23") (pintype "bidirectional"))
    )
    (net (code "124") (name "unconnected-(U$1-PadCN10_25)") (class "Default")
      (node (ref "U$1") (pin "CN10_25") (pinfunction "CN10_25_CN10_25") (pintype "bidirectional"))
    )
    (net (code "125") (name "unconnected-(U$1-PadCN10_27)") (class "Default")
      (node (ref "U$1") (pin "CN10_27") (pinfunction "CN10_27_CN10_27") (pintype "bidirectional"))
    )
    (net (code "126") (name "unconnected-(U$1-PadCN10_29)") (class "Default")
      (node (ref "U$1") (pin "CN10_29") (pinfunction "CN10_29_CN10_29") (pintype "bidirectional"))
    )
    (net (code "127") (name "unconnected-(U$1-PadCN10_31)") (class "Default")
      (node (ref "U$1") (pin "CN10_31") (pinfunction "CN10_31_CN10_31") (pintype "bidirectional"))
    )
    (net (code "128") (name "unconnected-(U$1-PadCN10_35)") (class "Default")
      (node (ref "U$1") (pin "CN10_35") (pinfunction "CN10_35_CN10_35") (pintype "bidirectional"))
    )
    (net (code "129") (name "unconnected-(U$1-PadCN10_37)") (class "Default")
      (node (ref "U$1") (pin "CN10_37") (pinfunction "CN10_37_CN10_37") (pintype "bidirectional"))
    )
  )
)
